# alarm_timing.net
KiCad netlist of a schematic drawn in Altium Designer
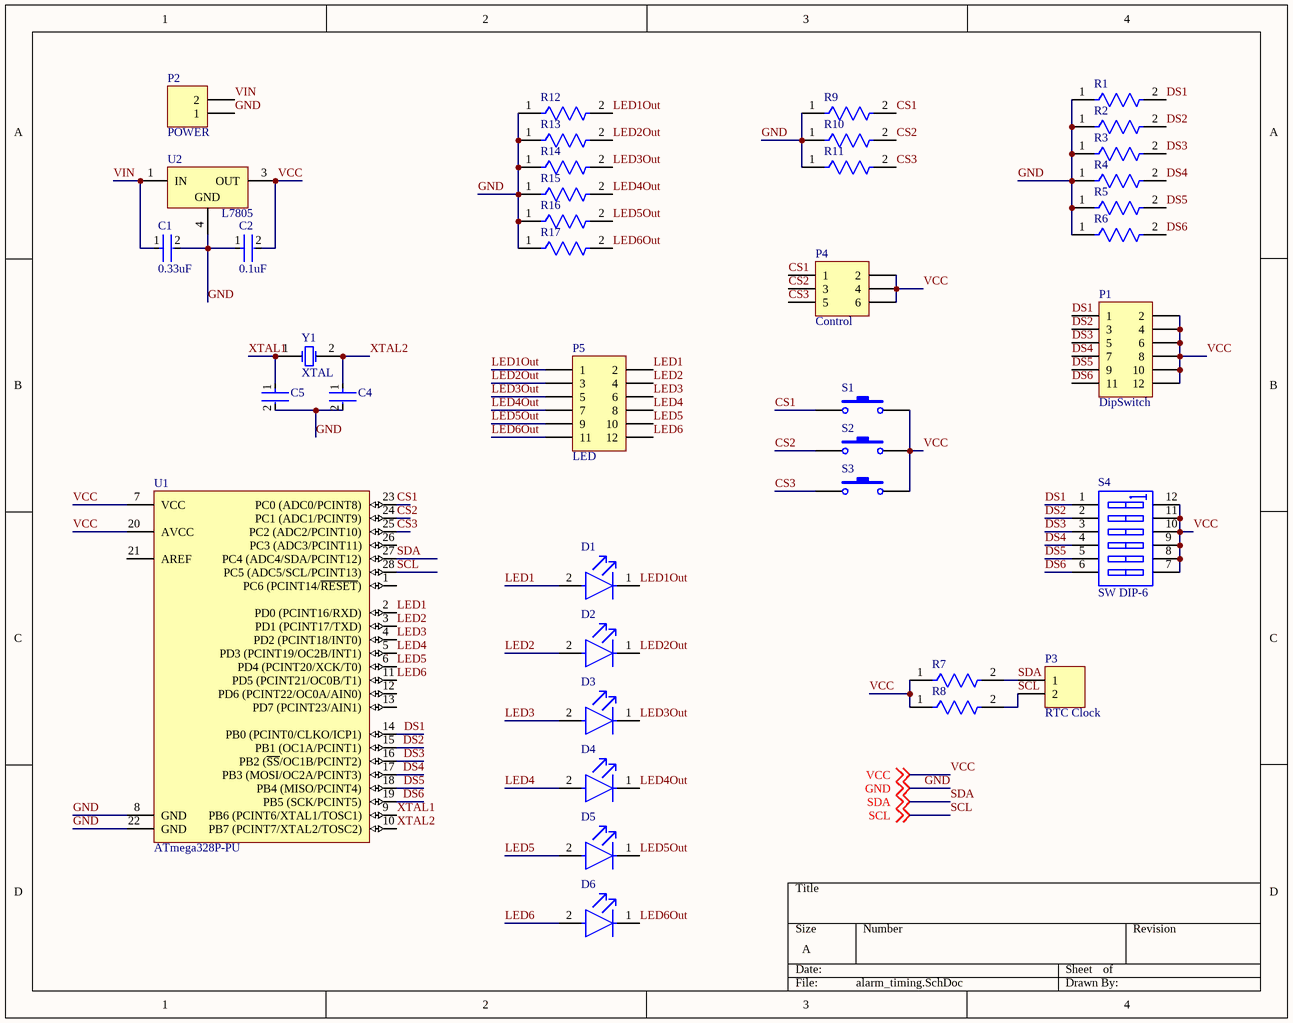
[diagram p0: alarm_timing.SchDoc]

(export (version "E")
  (design (tool "Eeschema 10.0.6"))
  (components
    (comp (ref "C1")
      (value "0.33uF")
      (footprint "FP-C1206C-EB-MFG")
      (description "1206 C 330nF Ceramic Multilayer Capacitor; 25 VDC; +125degC; X7R Dielec; +/-10%")
      (fields
        (field (name "MANUFACTURER") "KEMET")
        (field (name "MANUFACTURER PART NUMBER") "C1206C334K3RACTU")
      )
      (libsource (lib "Altium Content Vault") (part "b4654b650e69147ec39a6b967a45e02"))
    )
    (comp (ref "C2")
      (value "0.1uF")
      (footprint "FP-C1206C-EB-MFG")
      (description "1206 C 330nF Ceramic Multilayer Capacitor; 25 VDC; +125degC; X7R Dielec; +/-10%")
      (fields
        (field (name "MANUFACTURER") "KEMET")
        (field (name "MANUFACTURER PART NUMBER") "C1206C334K3RACTU")
      )
      (libsource (lib "Altium Content Vault") (part "b4654b650e69147ec39a6b967a45e02"))
    )
    (comp (ref "C4")
      (value "~")
      (footprint "FP-C1206C-EB-MFG")
      (description "C1206 0.10 μF X7R 10.00% 100 V")
      (fields (field (name "TOLERANCE") "0.1"))
      (libsource (lib "Altium Content Vault") (part "b4654b650e69147ec39a6b967a45e02"))
    )
    (comp (ref "C5")
      (value "~")
      (footprint "FP-C1206C-EB-MFG")
      (description "C1206 0.10 μF X7R 10.00% 100 V")
      (fields (field (name "TOLERANCE") "0.1"))
      (libsource (lib "Altium Content Vault") (part "b4654b650e69147ec39a6b967a45e02"))
    )
    (comp (ref "D1")
      (value "~")
      (footprint "FP-598-82-MFG")
      (description "LED RED CLEAR 1206 SMD")
      (fields
        (field (name "MANUFACTURER PART NUMBER") "598-8210-107F")
        (field (name "OCTOPART") "https://octopart.com/598-8210-107f-dialight-868600")
      )
      (libsource (lib "Altium Content Vault") (part "8706943c75ba83719d021d2fdc84c58"))
    )
    (comp (ref "D2")
      (value "~")
      (footprint "FP-598-82-MFG")
      (description "LED RED CLEAR 1206 SMD")
      (fields
        (field (name "MANUFACTURER PART NUMBER") "598-8210-107F")
        (field (name "OCTOPART") "https://octopart.com/598-8210-107f-dialight-868600")
      )
      (libsource (lib "Altium Content Vault") (part "8706943c75ba83719d021d2fdc84c58"))
    )
    (comp (ref "D3")
      (value "~")
      (footprint "FP-598-82-MFG")
      (description "LED RED CLEAR 1206 SMD")
      (fields
        (field (name "MANUFACTURER PART NUMBER") "598-8210-107F")
        (field (name "OCTOPART") "https://octopart.com/598-8210-107f-dialight-868600")
      )
      (libsource (lib "Altium Content Vault") (part "8706943c75ba83719d021d2fdc84c58"))
    )
    (comp (ref "D4")
      (value "~")
      (footprint "FP-598-82-MFG")
      (description "LED RED CLEAR 1206 SMD")
      (fields
        (field (name "MANUFACTURER PART NUMBER") "598-8210-107F")
        (field (name "OCTOPART") "https://octopart.com/598-8210-107f-dialight-868600")
      )
      (libsource (lib "Altium Content Vault") (part "8706943c75ba83719d021d2fdc84c58"))
    )
    (comp (ref "D5")
      (value "~")
      (footprint "FP-598-82-MFG")
      (description "LED RED CLEAR 1206 SMD")
      (fields
        (field (name "MANUFACTURER PART NUMBER") "598-8210-107F")
        (field (name "OCTOPART") "https://octopart.com/598-8210-107f-dialight-868600")
      )
      (libsource (lib "Altium Content Vault") (part "8706943c75ba83719d021d2fdc84c58"))
    )
    (comp (ref "D6")
      (value "~")
      (footprint "FP-598-82-MFG")
      (description "LED RED CLEAR 1206 SMD")
      (fields
        (field (name "MANUFACTURER PART NUMBER") "598-8210-107F")
        (field (name "OCTOPART") "https://octopart.com/598-8210-107f-dialight-868600")
      )
      (libsource (lib "Altium Content Vault") (part "8706943c75ba83719d021d2fdc84c58"))
    )
    (comp (ref "P1")
      (value "DipSwitch")
      (footprint "HDR2X6")
      (description "Header, 6-Pin, Dual row")
      (fields (field (name "PUBLISHER") "Altium Limited"))
      (libsource (lib "Miscellaneous Connectors") (part "Header 6X2"))
    )
    (comp (ref "P2")
      (value "POWER")
      (footprint "HDR1X2")
      (description "Header, 2-Pin")
      (fields (field (name "PUBLISHER") "Altium Limited"))
      (libsource (lib "Miscellaneous Connectors") (part "Header 2"))
    )
    (comp (ref "P3")
      (value "RTC Clock")
      (footprint "HDR1X2")
      (description "Header, 2-Pin")
      (fields (field (name "PUBLISHER") "Altium Limited"))
      (libsource (lib "") (part "Header 2_1"))
    )
    (comp (ref "P4")
      (value "Control")
      (footprint "HDR2X3")
      (description "Header, 3-Pin, Dual row")
      (fields (field (name "PUBLISHER") "Altium Limited"))
      (libsource (lib "Miscellaneous Connectors") (part "Header 3X2"))
    )
    (comp (ref "P5")
      (value "LED")
      (footprint "HDR2X6")
      (description "Header, 6-Pin, Dual row")
      (fields (field (name "PUBLISHER") "Altium Limited"))
      (libsource (lib "Miscellaneous Connectors") (part "Header 6X2"))
    )
    (comp (ref "R1")
      (value "~")
      (footprint "FP-CR1206-IPC_B")
      (description "Thick Film Chip Resistors 1206 10kΩ 0.25W 5% 200ppm/°C")
      (fields (field (name "TOLERANCE") "5%"))
      (libsource (lib "Altium Content Vault") (part "1029c3af85768c4190bb7ad29bc67b5"))
    )
    (comp (ref "R2")
      (value "~")
      (footprint "FP-CR1206-IPC_B")
      (description "Thick Film Chip Resistors 1206 10kΩ 0.25W 5% 200ppm/°C")
      (fields (field (name "TOLERANCE") "5%"))
      (libsource (lib "Altium Content Vault") (part "1029c3af85768c4190bb7ad29bc67b5"))
    )
    (comp (ref "R3")
      (value "~")
      (footprint "FP-CR1206-IPC_B")
      (description "Thick Film Chip Resistors 1206 10kΩ 0.25W 5% 200ppm/°C")
      (fields (field (name "TOLERANCE") "5%"))
      (libsource (lib "Altium Content Vault") (part "1029c3af85768c4190bb7ad29bc67b5"))
    )
    (comp (ref "R4")
      (value "~")
      (footprint "FP-CR1206-IPC_B")
      (description "Thick Film Chip Resistors 1206 10kΩ 0.25W 5% 200ppm/°C")
      (fields (field (name "TOLERANCE") "5%"))
      (libsource (lib "Altium Content Vault") (part "1029c3af85768c4190bb7ad29bc67b5"))
    )
    (comp (ref "R5")
      (value "~")
      (footprint "FP-CR1206-IPC_B")
      (description "Thick Film Chip Resistors 1206 10kΩ 0.25W 5% 200ppm/°C")
      (fields (field (name "TOLERANCE") "5%"))
      (libsource (lib "Altium Content Vault") (part "1029c3af85768c4190bb7ad29bc67b5"))
    )
    (comp (ref "R6")
      (value "~")
      (footprint "FP-CR1206-IPC_B")
      (description "Thick Film Chip Resistors 1206 10kΩ 0.25W 5% 200ppm/°C")
      (fields (field (name "TOLERANCE") "5%"))
      (libsource (lib "Altium Content Vault") (part "1029c3af85768c4190bb7ad29bc67b5"))
    )
    (comp (ref "R7")
      (value "~")
      (footprint "FP-CR1206-IPC_B")
      (description "Thick Film Chip Resistors 1206 10kΩ 0.25W 5% 200ppm/°C")
      (fields (field (name "TOLERANCE") "5%"))
      (libsource (lib "Altium Content Vault") (part "1029c3af85768c4190bb7ad29bc67b5"))
    )
    (comp (ref "R8")
      (value "~")
      (footprint "FP-CR1206-IPC_B")
      (description "Thick Film Chip Resistors 1206 10kΩ 0.25W 5% 200ppm/°C")
      (fields (field (name "TOLERANCE") "5%"))
      (libsource (lib "Altium Content Vault") (part "1029c3af85768c4190bb7ad29bc67b5"))
    )
    (comp (ref "R9")
      (value "~")
      (footprint "FP-CR1206-IPC_B")
      (description "Thick Film Chip Resistors 1206 10kΩ 0.25W 5% 200ppm/°C")
      (fields (field (name "TOLERANCE") "5%"))
      (libsource (lib "Altium Content Vault") (part "1029c3af85768c4190bb7ad29bc67b5"))
    )
    (comp (ref "R10")
      (value "~")
      (footprint "FP-CR1206-IPC_B")
      (description "Thick Film Chip Resistors 1206 10kΩ 0.25W 5% 200ppm/°C")
      (fields (field (name "TOLERANCE") "5%"))
      (libsource (lib "Altium Content Vault") (part "1029c3af85768c4190bb7ad29bc67b5"))
    )
    (comp (ref "R11")
      (value "~")
      (footprint "FP-CR1206-IPC_B")
      (description "Thick Film Chip Resistors 1206 10kΩ 0.25W 5% 200ppm/°C")
      (fields (field (name "TOLERANCE") "5%"))
      (libsource (lib "Altium Content Vault") (part "1029c3af85768c4190bb7ad29bc67b5"))
    )
    (comp (ref "R12")
      (value "~")
      (footprint "FP-CR1206-IPC_B")
      (description "Thick Film Chip Resistors 1206 10kΩ 0.25W 5% 200ppm/°C")
      (fields (field (name "TOLERANCE") "5%"))
      (libsource (lib "Altium Content Vault") (part "1029c3af85768c4190bb7ad29bc67b5"))
    )
    (comp (ref "R13")
      (value "~")
      (footprint "FP-CR1206-IPC_B")
      (description "Thick Film Chip Resistors 1206 10kΩ 0.25W 5% 200ppm/°C")
      (fields (field (name "TOLERANCE") "5%"))
      (libsource (lib "Altium Content Vault") (part "1029c3af85768c4190bb7ad29bc67b5"))
    )
    (comp (ref "R14")
      (value "~")
      (footprint "FP-CR1206-IPC_B")
      (description "Thick Film Chip Resistors 1206 10kΩ 0.25W 5% 200ppm/°C")
      (fields (field (name "TOLERANCE") "5%"))
      (libsource (lib "Altium Content Vault") (part "1029c3af85768c4190bb7ad29bc67b5"))
    )
    (comp (ref "R15")
      (value "~")
      (footprint "FP-CR1206-IPC_B")
      (description "Thick Film Chip Resistors 1206 10kΩ 0.25W 5% 200ppm/°C")
      (fields (field (name "TOLERANCE") "5%"))
      (libsource (lib "Altium Content Vault") (part "1029c3af85768c4190bb7ad29bc67b5"))
    )
    (comp (ref "R16")
      (value "~")
      (footprint "FP-CR1206-IPC_B")
      (description "Thick Film Chip Resistors 1206 10kΩ 0.25W 5% 200ppm/°C")
      (fields (field (name "TOLERANCE") "5%"))
      (libsource (lib "Altium Content Vault") (part "1029c3af85768c4190bb7ad29bc67b5"))
    )
    (comp (ref "R17")
      (value "~")
      (footprint "FP-CR1206-IPC_B")
      (description "Thick Film Chip Resistors 1206 10kΩ 0.25W 5% 200ppm/°C")
      (fields (field (name "TOLERANCE") "5%"))
      (libsource (lib "Altium Content Vault") (part "1029c3af85768c4190bb7ad29bc67b5"))
    )
    (comp (ref "S1")
      (value "~")
      (footprint "SPST-2")
      (description "Switch")
      (fields (field (name "PUBLISHER") "Altium Limited"))
      (libsource (lib "Miscellaneous Devices") (part "SW-PB"))
    )
    (comp (ref "S2")
      (value "~")
      (footprint "SPST-2")
      (description "Switch")
      (fields (field (name "PUBLISHER") "Altium Limited"))
      (libsource (lib "Miscellaneous Devices") (part "SW-PB"))
    )
    (comp (ref "S3")
      (value "~")
      (footprint "SPST-2")
      (description "Switch")
      (fields (field (name "PUBLISHER") "Altium Limited"))
      (libsource (lib "Miscellaneous Devices") (part "SW-PB"))
    )
    (comp (ref "S4")
      (value "SW DIP-6")
      (footprint "DIP-12/SW")
      (description "DIP Switch, 6 Position, SPST")
      (fields (field (name "PUBLISHER") "Altium Limited"))
      (libsource (lib "Miscellaneous Devices") (part "SW DIP-6"))
    )
    (comp (ref "U1")
      (value "ATmega328P-PU")
      (footprint "28P3")
      (libsource (lib "Altium Content Vault") (part "MC-8B-ATM48-IL28"))
    )
    (comp (ref "U2")
      (value "L7805")
      (footprint "TO-263_N")
      (description "Positive Voltage Regulator, 3-Pin D2PAK, Tape and Reel")
      (libsource (lib "Altium Content Vault") (part "PM-REG-L4940-SOT3"))
    )
    (comp (ref "Y1")
      (value "XTAL")
      (footprint "R38")
      (description "Crystal Oscillator")
      (fields (field (name "PUBLISHER") "Altium Limited"))
      (libsource (lib "Miscellaneous Devices") (part "XTAL"))
    )
  )
  (nets
    (net (code "1") (name "/CS1") (class "Default")
      (node (ref "P4") (pin "1") (pinfunction "1_1") (pintype "passive"))
      (node (ref "R9") (pin "2") (pinfunction "2_2") (pintype "passive"))
      (node (ref "S1") (pin "1") (pinfunction "1_1") (pintype "passive"))
      (node (ref "U1") (pin "23") (pinfunction "PC0_(ADC0/PCINT8)_23") (pintype "bidirectional"))
    )
    (net (code "2") (name "/CS2") (class "Default")
      (node (ref "P4") (pin "3") (pinfunction "3_3") (pintype "passive"))
      (node (ref "R10") (pin "2") (pinfunction "2_2") (pintype "passive"))
      (node (ref "S2") (pin "1") (pinfunction "1_1") (pintype "passive"))
      (node (ref "U1") (pin "24") (pinfunction "PC1_(ADC1/PCINT9)_24") (pintype "bidirectional"))
    )
    (net (code "3") (name "/CS3") (class "Default")
      (node (ref "P4") (pin "5") (pinfunction "5_5") (pintype "passive"))
      (node (ref "R11") (pin "2") (pinfunction "2_2") (pintype "passive"))
      (node (ref "S3") (pin "1") (pinfunction "1_1") (pintype "passive"))
      (node (ref "U1") (pin "25") (pinfunction "PC2_(ADC2/PCINT10)_25") (pintype "bidirectional"))
    )
    (net (code "4") (name "/DS1") (class "Default")
      (node (ref "P1") (pin "1") (pinfunction "1_1") (pintype "passive"))
      (node (ref "R1") (pin "2") (pinfunction "2_2") (pintype "passive"))
      (node (ref "S4") (pin "1") (pinfunction "A1_1") (pintype "passive"))
      (node (ref "U1") (pin "14") (pinfunction "PB0_(PCINT0/CLKO/ICP1)_14") (pintype "bidirectional"))
    )
    (net (code "5") (name "/DS2") (class "Default")
      (node (ref "P1") (pin "3") (pinfunction "3_3") (pintype "passive"))
      (node (ref "R2") (pin "2") (pinfunction "2_2") (pintype "passive"))
      (node (ref "S4") (pin "2") (pinfunction "A2_2") (pintype "passive"))
      (node (ref "U1") (pin "15") (pinfunction "PB1_(OC1A/PCINT1)_15") (pintype "bidirectional"))
    )
    (net (code "6") (name "/DS3") (class "Default")
      (node (ref "P1") (pin "5") (pinfunction "5_5") (pintype "passive"))
      (node (ref "R3") (pin "2") (pinfunction "2_2") (pintype "passive"))
      (node (ref "S4") (pin "3") (pinfunction "A3_3") (pintype "passive"))
      (node (ref "U1") (pin "16") (pinfunction "PB2_(~{SS}/OC1B/PCINT2)_16") (pintype "bidirectional"))
    )
    (net (code "7") (name "/DS4") (class "Default")
      (node (ref "P1") (pin "7") (pinfunction "7_7") (pintype "passive"))
      (node (ref "R4") (pin "2") (pinfunction "2_2") (pintype "passive"))
      (node (ref "S4") (pin "4") (pinfunction "A4_4") (pintype "passive"))
      (node (ref "U1") (pin "17") (pinfunction "PB3_(MOSI/OC2A/PCINT3)_17") (pintype "bidirectional"))
    )
    (net (code "8") (name "/DS5") (class "Default")
      (node (ref "P1") (pin "9") (pinfunction "9_9") (pintype "passive"))
      (node (ref "R5") (pin "2") (pinfunction "2_2") (pintype "passive"))
      (node (ref "S4") (pin "5") (pinfunction "A5_5") (pintype "passive"))
      (node (ref "U1") (pin "18") (pinfunction "PB4_(MISO/PCINT4)_18") (pintype "bidirectional"))
    )
    (net (code "9") (name "/DS6") (class "Default")
      (node (ref "P1") (pin "11") (pinfunction "11_11") (pintype "passive"))
      (node (ref "R6") (pin "2") (pinfunction "2_2") (pintype "passive"))
      (node (ref "S4") (pin "6") (pinfunction "A6_6") (pintype "passive"))
      (node (ref "U1") (pin "19") (pinfunction "PB5_(SCK/PCINT5)_19") (pintype "bidirectional"))
    )
    (net (code "10") (name "/LED1") (class "Default")
      (node (ref "D1") (pin "2") (pinfunction "A_2") (pintype "passive"))
      (node (ref "P5") (pin "2") (pinfunction "2_2") (pintype "passive"))
      (node (ref "U1") (pin "2") (pinfunction "PD0_(PCINT16/RXD)_2") (pintype "bidirectional"))
    )
    (net (code "11") (name "/LED1Out") (class "Default")
      (node (ref "D1") (pin "1") (pinfunction "C_1") (pintype "passive"))
      (node (ref "P5") (pin "1") (pinfunction "1_1") (pintype "passive"))
      (node (ref "R12") (pin "2") (pinfunction "2_2") (pintype "passive"))
    )
    (net (code "12") (name "/LED2") (class "Default")
      (node (ref "D2") (pin "2") (pinfunction "A_2") (pintype "passive"))
      (node (ref "P5") (pin "4") (pinfunction "4_4") (pintype "passive"))
      (node (ref "U1") (pin "3") (pinfunction "PD1_(PCINT17/TXD)_3") (pintype "bidirectional"))
    )
    (net (code "13") (name "/LED2Out") (class "Default")
      (node (ref "D2") (pin "1") (pinfunction "C_1") (pintype "passive"))
      (node (ref "P5") (pin "3") (pinfunction "3_3") (pintype "passive"))
      (node (ref "R13") (pin "2") (pinfunction "2_2") (pintype "passive"))
    )
    (net (code "14") (name "/LED3") (class "Default")
      (node (ref "D3") (pin "2") (pinfunction "A_2") (pintype "passive"))
      (node (ref "P5") (pin "6") (pinfunction "6_6") (pintype "passive"))
      (node (ref "U1") (pin "4") (pinfunction "PD2_(PCINT18/INT0)_4") (pintype "bidirectional"))
    )
    (net (code "15") (name "/LED3Out") (class "Default")
      (node (ref "D3") (pin "1") (pinfunction "C_1") (pintype "passive"))
      (node (ref "P5") (pin "5") (pinfunction "5_5") (pintype "passive"))
      (node (ref "R14") (pin "2") (pinfunction "2_2") (pintype "passive"))
    )
    (net (code "16") (name "/LED4") (class "Default")
      (node (ref "D4") (pin "2") (pinfunction "A_2") (pintype "passive"))
      (node (ref "P5") (pin "8") (pinfunction "8_8") (pintype "passive"))
      (node (ref "U1") (pin "5") (pinfunction "PD3_(PCINT19/OC2B/INT1)_5") (pintype "bidirectional"))
    )
    (net (code "17") (name "/LED4Out") (class "Default")
      (node (ref "D4") (pin "1") (pinfunction "C_1") (pintype "passive"))
      (node (ref "P5") (pin "7") (pinfunction "7_7") (pintype "passive"))
      (node (ref "R15") (pin "2") (pinfunction "2_2") (pintype "passive"))
    )
    (net (code "18") (name "/LED5") (class "Default")
      (node (ref "D5") (pin "2") (pinfunction "A_2") (pintype "passive"))
      (node (ref "P5") (pin "10") (pinfunction "10_10") (pintype "passive"))
      (node (ref "U1") (pin "6") (pinfunction "PD4_(PCINT20/XCK/T0)_6") (pintype "bidirectional"))
    )
    (net (code "19") (name "/LED5Out") (class "Default")
      (node (ref "D5") (pin "1") (pinfunction "C_1") (pintype "passive"))
      (node (ref "P5") (pin "9") (pinfunction "9_9") (pintype "passive"))
      (node (ref "R16") (pin "2") (pinfunction "2_2") (pintype "passive"))
    )
    (net (code "20") (name "/LED6") (class "Default")
      (node (ref "D6") (pin "2") (pinfunction "A_2") (pintype "passive"))
      (node (ref "P5") (pin "12") (pinfunction "12_12") (pintype "passive"))
      (node (ref "U1") (pin "11") (pinfunction "PD5_(PCINT21/OC0B/T1)_11") (pintype "bidirectional"))
    )
    (net (code "21") (name "/LED6Out") (class "Default")
      (node (ref "D6") (pin "1") (pinfunction "C_1") (pintype "passive"))
      (node (ref "P5") (pin "11") (pinfunction "11_11") (pintype "passive"))
      (node (ref "R17") (pin "2") (pinfunction "2_2") (pintype "passive"))
    )
    (net (code "22") (name "/VIN") (class "Default")
      (node (ref "C1") (pin "1") (pinfunction "1_1") (pintype "passive"))
      (node (ref "P2") (pin "2") (pinfunction "2_2") (pintype "passive"))
      (node (ref "U2") (pin "1") (pinfunction "IN_1") (pintype "power_in"))
    )
    (net (code "23") (name "/XTAL1") (class "Default")
      (node (ref "C5") (pin "1") (pinfunction "1_1") (pintype "passive"))
      (node (ref "U1") (pin "9") (pinfunction "PB6_(PCINT6/XTAL1/TOSC1)_9") (pintype "bidirectional"))
      (node (ref "Y1") (pin "1") (pinfunction "OSC1_1") (pintype "passive"))
    )
    (net (code "24") (name "/XTAL2") (class "Default")
      (node (ref "C4") (pin "1") (pinfunction "1_1") (pintype "passive"))
      (node (ref "U1") (pin "10") (pinfunction "PB7_(PCINT7/XTAL2/TOSC2)_10") (pintype "bidirectional"))
      (node (ref "Y1") (pin "2") (pinfunction "OSC2_2") (pintype "passive"))
    )
    (net (code "25") (name "GND") (class "Default")
      (node (ref "C1") (pin "2") (pinfunction "2_2") (pintype "passive"))
      (node (ref "C2") (pin "1") (pinfunction "1_1") (pintype "passive"))
      (node (ref "C4") (pin "2") (pinfunction "2_2") (pintype "passive"))
      (node (ref "C5") (pin "2") (pinfunction "2_2") (pintype "passive"))
      (node (ref "P2") (pin "1") (pinfunction "1_1") (pintype "passive"))
      (node (ref "R1") (pin "1") (pinfunction "1_1") (pintype "passive"))
      (node (ref "R10") (pin "1") (pinfunction "1_1") (pintype "passive"))
      (node (ref "R11") (pin "1") (pinfunction "1_1") (pintype "passive"))
      (node (ref "R12") (pin "1") (pinfunction "1_1") (pintype "passive"))
      (node (ref "R13") (pin "1") (pinfunction "1_1") (pintype "passive"))
      (node (ref "R14") (pin "1") (pinfunction "1_1") (pintype "passive"))
      (node (ref "R15") (pin "1") (pinfunction "1_1") (pintype "passive"))
      (node (ref "R16") (pin "1") (pinfunction "1_1") (pintype "passive"))
      (node (ref "R17") (pin "1") (pinfunction "1_1") (pintype "passive"))
      (node (ref "R2") (pin "1") (pinfunction "1_1") (pintype "passive"))
      (node (ref "R3") (pin "1") (pinfunction "1_1") (pintype "passive"))
      (node (ref "R4") (pin "1") (pinfunction "1_1") (pintype "passive"))
      (node (ref "R5") (pin "1") (pinfunction "1_1") (pintype "passive"))
      (node (ref "R6") (pin "1") (pinfunction "1_1") (pintype "passive"))
      (node (ref "R9") (pin "1") (pinfunction "1_1") (pintype "passive"))
      (node (ref "U1") (pin "22") (pinfunction "GND_22") (pintype "power_in"))
      (node (ref "U1") (pin "8") (pinfunction "GND_8") (pintype "power_in"))
      (node (ref "U2") (pin "4") (pinfunction "GND_4") (pintype "power_in"))
    )
    (net (code "26") (name "SCL") (class "Default")
      (node (ref "P3") (pin "2") (pinfunction "2_2") (pintype "passive"))
      (node (ref "R8") (pin "2") (pinfunction "2_2") (pintype "passive"))
      (node (ref "U1") (pin "28") (pinfunction "PC5_(ADC5/SCL/PCINT13)_28") (pintype "bidirectional"))
    )
    (net (code "27") (name "SDA") (class "Default")
      (node (ref "P3") (pin "1") (pinfunction "1_1") (pintype "passive"))
      (node (ref "R7") (pin "2") (pinfunction "2_2") (pintype "passive"))
      (node (ref "U1") (pin "27") (pinfunction "PC4_(ADC4/SDA/PCINT12)_27") (pintype "bidirectional"))
    )
    (net (code "28") (name "VCC") (class "Default")
      (node (ref "C2") (pin "2") (pinfunction "2_2") (pintype "passive"))
      (node (ref "P1") (pin "10") (pinfunction "10_10") (pintype "passive"))
      (node (ref "P1") (pin "12") (pinfunction "12_12") (pintype "passive"))
      (node (ref "P1") (pin "2") (pinfunction "2_2") (pintype "passive"))
      (node (ref "P1") (pin "4") (pinfunction "4_4") (pintype "passive"))
      (node (ref "P1") (pin "6") (pinfunction "6_6") (pintype "passive"))
      (node (ref "P1") (pin "8") (pinfunction "8_8") (pintype "passive"))
      (node (ref "P4") (pin "2") (pinfunction "2_2") (pintype "passive"))
      (node (ref "P4") (pin "4") (pinfunction "4_4") (pintype "passive"))
      (node (ref "P4") (pin "6") (pinfunction "6_6") (pintype "passive"))
      (node (ref "R7") (pin "1") (pinfunction "1_1") (pintype "passive"))
      (node (ref "R8") (pin "1") (pinfunction "1_1") (pintype "passive"))
      (node (ref "S1") (pin "2") (pinfunction "2_2") (pintype "passive"))
      (node (ref "S2") (pin "2") (pinfunction "2_2") (pintype "passive"))
      (node (ref "S3") (pin "2") (pinfunction "2_2") (pintype "passive"))
      (node (ref "S4") (pin "10") (pinfunction "B3_10") (pintype "passive"))
      (node (ref "S4") (pin "11") (pinfunction "B2_11") (pintype "passive"))
      (node (ref "S4") (pin "12") (pinfunction "B1_12") (pintype "passive"))
      (node (ref "S4") (pin "7") (pinfunction "B6_7") (pintype "passive"))
      (node (ref "S4") (pin "8") (pinfunction "B5_8") (pintype "passive"))
      (node (ref "S4") (pin "9") (pinfunction "B4_9") (pintype "passive"))
      (node (ref "U1") (pin "20") (pinfunction "AVCC_20") (pintype "power_in"))
      (node (ref "U1") (pin "7") (pinfunction "VCC_7") (pintype "power_in"))
      (node (ref "U2") (pin "3") (pinfunction "OUT_3") (pintype "power_in"))
    )
    (net (code "29") (name "unconnected-(U1-AREF-Pad21)") (class "Default")
      (node (ref "U1") (pin "21") (pinfunction "AREF_21") (pintype "power_in"))
    )
    (net (code "30") (name "unconnected-(U1-PC3_(ADC3{slash}PCINT11)-Pad26)") (class "Default")
      (node (ref "U1") (pin "26") (pinfunction "PC3_(ADC3/PCINT11)_26") (pintype "bidirectional"))
    )
    (net (code "31") (name "unconnected-(U1-PC6_(PCINT14{slash}~{RESET})-Pad1)") (class "Default")
      (node (ref "U1") (pin "1") (pinfunction "PC6_(PCINT14/~{RESET})_1") (pintype "bidirectional"))
    )
    (net (code "32") (name "unconnected-(U1-PD6_(PCINT22{slash}OC0A{slash}AIN0)-Pad12)") (class "Default")
      (node (ref "U1") (pin "12") (pinfunction "PD6_(PCINT22/OC0A/AIN0)_12") (pintype "bidirectional"))
    )
    (net (code "33") (name "unconnected-(U1-PD7_(PCINT23{slash}AIN1)-Pad13)") (class "Default")
      (node (ref "U1") (pin "13") (pinfunction "PD7_(PCINT23/AIN1)_13") (pintype "bidirectional"))
    )
  )
)
